# DW1000.net
KiCad netlist of a schematic drawn in Altium Designer
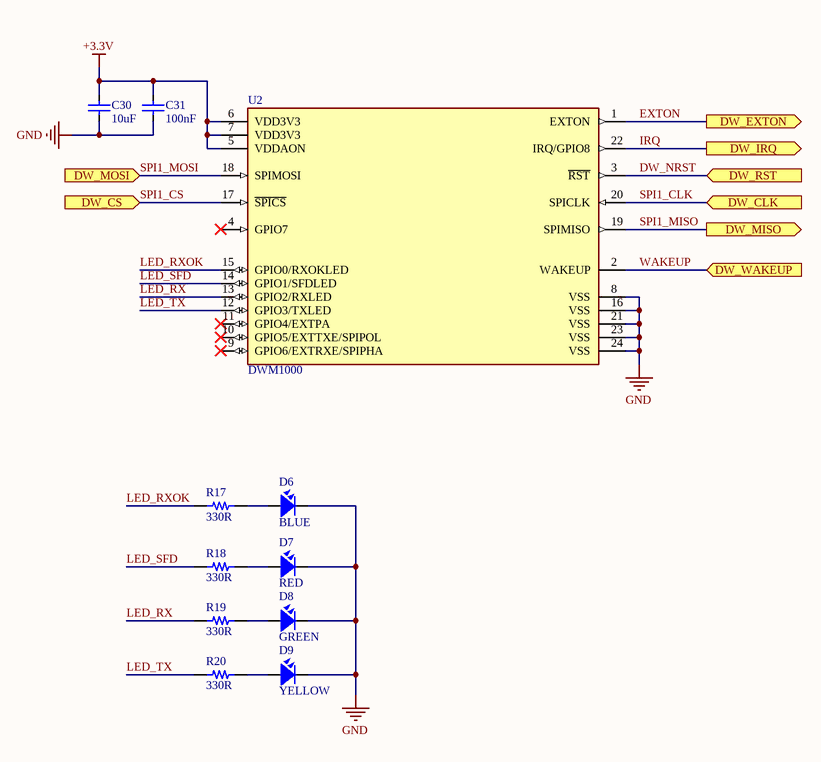
[diagram p0: DW1000.SchDoc]

(export (version "E")
  (design (tool "Eeschema 10.0.6"))
  (components
    (comp (ref "C30")
      (value "10uF")
      (footprint "CAP_0603")
      (description "Capacitor")
      (fields (field (name "PUBLISHER") "Altium Limited"))
      (libsource (lib "My Library") (part "CapSMD"))
    )
    (comp (ref "C31")
      (value "100nF")
      (footprint "CAP_0603")
      (description "Capacitor")
      (fields (field (name "PUBLISHER") "Altium Limited"))
      (libsource (lib "My Library") (part "CapSMD"))
    )
    (comp (ref "D6")
      (value "BLUE")
      (footprint "LED-0603-Green")
      (description "LED Single colour Green and Red")
      (libsource (lib "My Library") (part "LED"))
    )
    (comp (ref "D7")
      (value "RED")
      (footprint "LED-0603-Red")
      (description "LED Single colour Green and Red")
      (libsource (lib "My Library") (part "LED"))
    )
    (comp (ref "D8")
      (value "GREEN")
      (footprint "LED-0603-Green")
      (description "LED Single colour Green and Red")
      (libsource (lib "My Library") (part "LED"))
    )
    (comp (ref "D9")
      (value "YELLOW")
      (footprint "LED-0603-Green")
      (description "LED Single colour Green and Red")
      (libsource (lib "My Library") (part "LED"))
    )
    (comp (ref "R17")
      (value "330R")
      (footprint "RES-SMD-0603")
      (description "Resistor")
      (fields
        (field (name "MANUFACTURER") "Generic Components")
        (field (name "PUBLISHER") "Altium Hobart Technology Centre")
      )
      (libsource (lib "My Library") (part "Resistor - SMD"))
    )
    (comp (ref "R18")
      (value "330R")
      (footprint "RES-SMD-0603")
      (description "Resistor")
      (fields
        (field (name "MANUFACTURER") "Generic Components")
        (field (name "PUBLISHER") "Altium Hobart Technology Centre")
      )
      (libsource (lib "My Library") (part "Resistor - SMD"))
    )
    (comp (ref "R19")
      (value "330R")
      (footprint "RES-SMD-0603")
      (description "Resistor")
      (fields
        (field (name "MANUFACTURER") "Generic Components")
        (field (name "PUBLISHER") "Altium Hobart Technology Centre")
      )
      (libsource (lib "My Library") (part "Resistor - SMD"))
    )
    (comp (ref "R20")
      (value "330R")
      (footprint "RES-SMD-0603")
      (description "Resistor")
      (fields
        (field (name "MANUFACTURER") "Generic Components")
        (field (name "PUBLISHER") "Altium Hobart Technology Centre")
      )
      (libsource (lib "My Library") (part "Resistor - SMD"))
    )
    (comp (ref "U2")
      (value "DWM1000")
      (footprint "DW1000")
      (description "Decawave's DW1000 Ultra\r\nWideband (UWB) transceiver IC")
      (libsource (lib "My Library") (part "DWM1000"))
    )
  )
  (nets
    (net (code "1") (name "+3.3V") (class "Default")
      (node (ref "C30") (pin "2") (pinfunction "2_2") (pintype "passive"))
      (node (ref "C31") (pin "2") (pinfunction "2_2") (pintype "passive"))
      (node (ref "U2") (pin "5") (pinfunction "VDDAON_5") (pintype "power_in"))
      (node (ref "U2") (pin "6") (pinfunction "VDD3V3_6") (pintype "power_in"))
      (node (ref "U2") (pin "7") (pinfunction "VDD3V3_7") (pintype "power_in"))
    )
    (net (code "2") (name "/DW_NRST") (class "Default")
      (node (ref "U2") (pin "3") (pinfunction "~{RST}_3") (pintype "output"))
    )
    (net (code "3") (name "/EXTON") (class "Default")
      (node (ref "U2") (pin "1") (pinfunction "EXTON_1") (pintype "output"))
    )
    (net (code "4") (name "/IRQ") (class "Default")
      (node (ref "U2") (pin "22") (pinfunction "IRQ/GPIO8_22") (pintype "output"))
    )
    (net (code "5") (name "/LED_RX") (class "Default")
      (node (ref "R19") (pin "2") (pinfunction "2_2") (pintype "passive"))
      (node (ref "U2") (pin "13") (pinfunction "GPIO2/RXLED_13") (pintype "bidirectional"))
    )
    (net (code "6") (name "/LED_RXOK") (class "Default")
      (node (ref "R17") (pin "2") (pinfunction "2_2") (pintype "passive"))
      (node (ref "U2") (pin "15") (pinfunction "GPIO0/RXOKLED_15") (pintype "bidirectional"))
    )
    (net (code "7") (name "/LED_SFD") (class "Default")
      (node (ref "R18") (pin "2") (pinfunction "2_2") (pintype "passive"))
      (node (ref "U2") (pin "14") (pinfunction "GPIO1/SFDLED_14") (pintype "bidirectional"))
    )
    (net (code "8") (name "/LED_TX") (class "Default")
      (node (ref "R20") (pin "2") (pinfunction "2_2") (pintype "passive"))
      (node (ref "U2") (pin "12") (pinfunction "GPIO3/TXLED_12") (pintype "bidirectional"))
    )
    (net (code "9") (name "/SPI1_CLK") (class "Default")
      (node (ref "U2") (pin "20") (pinfunction "SPICLK_20") (pintype "input"))
    )
    (net (code "10") (name "/SPI1_CS") (class "Default")
      (node (ref "U2") (pin "17") (pinfunction "~{SPICS}_17") (pintype "input"))
    )
    (net (code "11") (name "/SPI1_MISO") (class "Default")
      (node (ref "U2") (pin "19") (pinfunction "SPIMISO_19") (pintype "output"))
    )
    (net (code "12") (name "/SPI1_MOSI") (class "Default")
      (node (ref "U2") (pin "18") (pinfunction "SPIMOSI_18") (pintype "input"))
    )
    (net (code "13") (name "/WAKEUP") (class "Default")
      (node (ref "U2") (pin "2") (pinfunction "WAKEUP_2") (pintype "passive"))
    )
    (net (code "14") (name "GND") (class "Default")
      (node (ref "C30") (pin "1") (pinfunction "1_1") (pintype "passive"))
      (node (ref "C31") (pin "1") (pinfunction "1_1") (pintype "passive"))
      (node (ref "D6") (pin "2") (pinfunction "2_2") (pintype "passive"))
      (node (ref "D7") (pin "2") (pinfunction "2_2") (pintype "passive"))
      (node (ref "D8") (pin "2") (pinfunction "2_2") (pintype "passive"))
      (node (ref "D9") (pin "2") (pinfunction "2_2") (pintype "passive"))
      (node (ref "U2") (pin "16") (pinfunction "VSS_16") (pintype "power_in"))
      (node (ref "U2") (pin "21") (pinfunction "VSS_21") (pintype "power_in"))
      (node (ref "U2") (pin "23") (pinfunction "VSS_23") (pintype "power_in"))
      (node (ref "U2") (pin "24") (pinfunction "VSS_24") (pintype "power_in"))
      (node (ref "U2") (pin "8") (pinfunction "VSS_8") (pintype "power_in"))
    )
    (net (code "15") (name "Net-(D6-Pad1)") (class "Default")
      (node (ref "D6") (pin "1") (pinfunction "1_1") (pintype "passive"))
      (node (ref "R17") (pin "1") (pinfunction "1_1") (pintype "passive"))
    )
    (net (code "16") (name "Net-(D7-Pad1)") (class "Default")
      (node (ref "D7") (pin "1") (pinfunction "1_1") (pintype "passive"))
      (node (ref "R18") (pin "1") (pinfunction "1_1") (pintype "passive"))
    )
    (net (code "17") (name "Net-(D8-Pad1)") (class "Default")
      (node (ref "D8") (pin "1") (pinfunction "1_1") (pintype "passive"))
      (node (ref "R19") (pin "1") (pinfunction "1_1") (pintype "passive"))
    )
    (net (code "18") (name "Net-(D9-Pad1)") (class "Default")
      (node (ref "D9") (pin "1") (pinfunction "1_1") (pintype "passive"))
      (node (ref "R20") (pin "1") (pinfunction "1_1") (pintype "passive"))
    )
    (net (code "19") (name "unconnected-(U2-GPIO4{slash}EXTPA-Pad11)") (class "Default")
      (node (ref "U2") (pin "11") (pinfunction "GPIO4/EXTPA_11") (pintype "bidirectional+no_connect"))
    )
    (net (code "20") (name "unconnected-(U2-GPIO5{slash}EXTTXE{slash}SPIPOL-Pad10)") (class "Default")
      (node (ref "U2") (pin "10") (pinfunction "GPIO5/EXTTXE/SPIPOL_10") (pintype "bidirectional+no_connect"))
    )
    (net (code "21") (name "unconnected-(U2-GPIO6{slash}EXTRXE{slash}SPIPHA-Pad9)") (class "Default")
      (node (ref "U2") (pin "9") (pinfunction "GPIO6/EXTRXE/SPIPHA_9") (pintype "bidirectional+no_connect"))
    )
    (net (code "22") (name "unconnected-(U2-GPIO7-Pad4)") (class "Default")
      (node (ref "U2") (pin "4") (pinfunction "GPIO7_4") (pintype "input+no_connect"))
    )
  )
)
